# MCULeds.net
KiCad netlist of a schematic drawn in Altium Designer
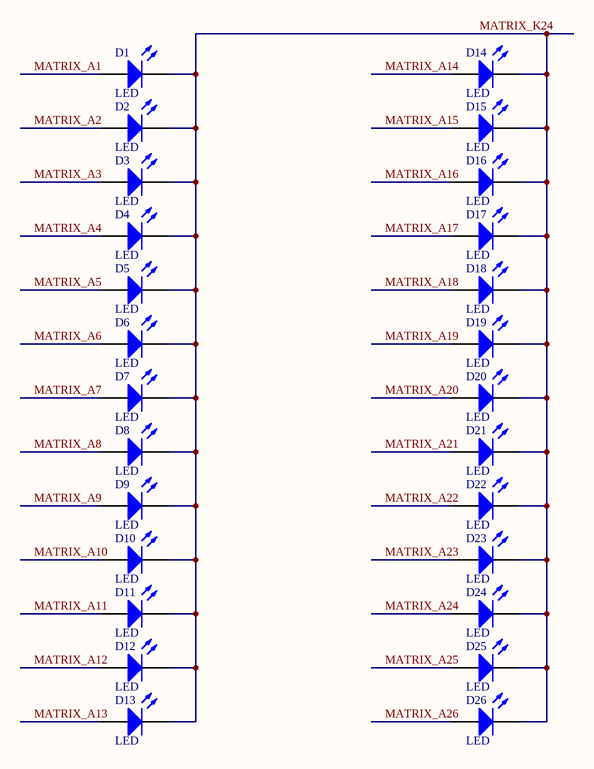
[diagram p0: MCULeds.SchDoc]

(export (version "E")
  (design (tool "Eeschema 10.0.6"))
  (components
    (comp (ref "D1")
      (value "LED")
      (footprint "led_0402")
      (description "Typical INFRARED GaAs LED")
      (fields (field (name "PUBLISHER") "Altium Limited"))
      (libsource (lib "Lib_Sch") (part "LED"))
    )
    (comp (ref "D2")
      (value "LED")
      (footprint "led_0402")
      (description "Typical INFRARED GaAs LED")
      (fields (field (name "PUBLISHER") "Altium Limited"))
      (libsource (lib "Lib_Sch") (part "LED"))
    )
    (comp (ref "D3")
      (value "LED")
      (footprint "led_0402")
      (description "Typical INFRARED GaAs LED")
      (fields (field (name "PUBLISHER") "Altium Limited"))
      (libsource (lib "Lib_Sch") (part "LED"))
    )
    (comp (ref "D4")
      (value "LED")
      (footprint "led_0402")
      (description "Typical INFRARED GaAs LED")
      (fields (field (name "PUBLISHER") "Altium Limited"))
      (libsource (lib "Lib_Sch") (part "LED"))
    )
    (comp (ref "D5")
      (value "LED")
      (footprint "led_0402")
      (description "Typical INFRARED GaAs LED")
      (fields (field (name "PUBLISHER") "Altium Limited"))
      (libsource (lib "Lib_Sch") (part "LED"))
    )
    (comp (ref "D6")
      (value "LED")
      (footprint "led_0402")
      (description "Typical INFRARED GaAs LED")
      (fields (field (name "PUBLISHER") "Altium Limited"))
      (libsource (lib "Lib_Sch") (part "LED"))
    )
    (comp (ref "D7")
      (value "LED")
      (footprint "led_0402")
      (description "Typical INFRARED GaAs LED")
      (fields (field (name "PUBLISHER") "Altium Limited"))
      (libsource (lib "Lib_Sch") (part "LED"))
    )
    (comp (ref "D8")
      (value "LED")
      (footprint "led_0402")
      (description "Typical INFRARED GaAs LED")
      (fields (field (name "PUBLISHER") "Altium Limited"))
      (libsource (lib "Lib_Sch") (part "LED"))
    )
    (comp (ref "D9")
      (value "LED")
      (footprint "led_0402")
      (description "Typical INFRARED GaAs LED")
      (fields (field (name "PUBLISHER") "Altium Limited"))
      (libsource (lib "Lib_Sch") (part "LED"))
    )
    (comp (ref "D10")
      (value "LED")
      (footprint "led_0402")
      (description "Typical INFRARED GaAs LED")
      (fields (field (name "PUBLISHER") "Altium Limited"))
      (libsource (lib "Lib_Sch") (part "LED"))
    )
    (comp (ref "D11")
      (value "LED")
      (footprint "led_0402")
      (description "Typical INFRARED GaAs LED")
      (fields (field (name "PUBLISHER") "Altium Limited"))
      (libsource (lib "Lib_Sch") (part "LED"))
    )
    (comp (ref "D12")
      (value "LED")
      (footprint "led_0402")
      (description "Typical INFRARED GaAs LED")
      (fields (field (name "PUBLISHER") "Altium Limited"))
      (libsource (lib "Lib_Sch") (part "LED"))
    )
    (comp (ref "D13")
      (value "LED")
      (footprint "led_0402")
      (description "Typical INFRARED GaAs LED")
      (fields (field (name "PUBLISHER") "Altium Limited"))
      (libsource (lib "Lib_Sch") (part "LED"))
    )
    (comp (ref "D14")
      (value "LED")
      (footprint "led_0402")
      (description "Typical INFRARED GaAs LED")
      (fields (field (name "PUBLISHER") "Altium Limited"))
      (libsource (lib "Lib_Sch") (part "LED"))
    )
    (comp (ref "D15")
      (value "LED")
      (footprint "led_0402")
      (description "Typical INFRARED GaAs LED")
      (fields (field (name "PUBLISHER") "Altium Limited"))
      (libsource (lib "Lib_Sch") (part "LED"))
    )
    (comp (ref "D16")
      (value "LED")
      (footprint "led_0402")
      (description "Typical INFRARED GaAs LED")
      (fields (field (name "PUBLISHER") "Altium Limited"))
      (libsource (lib "Lib_Sch") (part "LED"))
    )
    (comp (ref "D17")
      (value "LED")
      (footprint "led_0402")
      (description "Typical INFRARED GaAs LED")
      (fields (field (name "PUBLISHER") "Altium Limited"))
      (libsource (lib "Lib_Sch") (part "LED"))
    )
    (comp (ref "D18")
      (value "LED")
      (footprint "led_0402")
      (description "Typical INFRARED GaAs LED")
      (fields (field (name "PUBLISHER") "Altium Limited"))
      (libsource (lib "Lib_Sch") (part "LED"))
    )
    (comp (ref "D19")
      (value "LED")
      (footprint "led_0402")
      (description "Typical INFRARED GaAs LED")
      (fields (field (name "PUBLISHER") "Altium Limited"))
      (libsource (lib "Lib_Sch") (part "LED"))
    )
    (comp (ref "D20")
      (value "LED")
      (footprint "led_0402")
      (description "Typical INFRARED GaAs LED")
      (fields (field (name "PUBLISHER") "Altium Limited"))
      (libsource (lib "Lib_Sch") (part "LED"))
    )
    (comp (ref "D21")
      (value "LED")
      (footprint "led_0402")
      (description "Typical INFRARED GaAs LED")
      (fields (field (name "PUBLISHER") "Altium Limited"))
      (libsource (lib "Lib_Sch") (part "LED"))
    )
    (comp (ref "D22")
      (value "LED")
      (footprint "led_0402")
      (description "Typical INFRARED GaAs LED")
      (fields (field (name "PUBLISHER") "Altium Limited"))
      (libsource (lib "Lib_Sch") (part "LED"))
    )
    (comp (ref "D23")
      (value "LED")
      (footprint "led_0402")
      (description "Typical INFRARED GaAs LED")
      (fields (field (name "PUBLISHER") "Altium Limited"))
      (libsource (lib "Lib_Sch") (part "LED"))
    )
    (comp (ref "D24")
      (value "LED")
      (footprint "led_0402")
      (description "Typical INFRARED GaAs LED")
      (fields (field (name "PUBLISHER") "Altium Limited"))
      (libsource (lib "Lib_Sch") (part "LED"))
    )
    (comp (ref "D25")
      (value "LED")
      (footprint "led_0402")
      (description "Typical INFRARED GaAs LED")
      (fields (field (name "PUBLISHER") "Altium Limited"))
      (libsource (lib "Lib_Sch") (part "LED"))
    )
    (comp (ref "D26")
      (value "LED")
      (footprint "led_0402")
      (description "Typical INFRARED GaAs LED")
      (fields (field (name "PUBLISHER") "Altium Limited"))
      (libsource (lib "Lib_Sch") (part "LED"))
    )
  )
  (nets
    (net (code "1") (name "/MATRIX_A1") (class "Default")
      (node (ref "D1") (pin "A") (pinfunction "A_A") (pintype "passive"))
    )
    (net (code "2") (name "/MATRIX_A2") (class "Default")
      (node (ref "D2") (pin "A") (pinfunction "A_A") (pintype "passive"))
    )
    (net (code "3") (name "/MATRIX_A3") (class "Default")
      (node (ref "D3") (pin "A") (pinfunction "A_A") (pintype "passive"))
    )
    (net (code "4") (name "/MATRIX_A4") (class "Default")
      (node (ref "D4") (pin "A") (pinfunction "A_A") (pintype "passive"))
    )
    (net (code "5") (name "/MATRIX_A5") (class "Default")
      (node (ref "D5") (pin "A") (pinfunction "A_A") (pintype "passive"))
    )
    (net (code "6") (name "/MATRIX_A6") (class "Default")
      (node (ref "D6") (pin "A") (pinfunction "A_A") (pintype "passive"))
    )
    (net (code "7") (name "/MATRIX_A7") (class "Default")
      (node (ref "D7") (pin "A") (pinfunction "A_A") (pintype "passive"))
    )
    (net (code "8") (name "/MATRIX_A8") (class "Default")
      (node (ref "D8") (pin "A") (pinfunction "A_A") (pintype "passive"))
    )
    (net (code "9") (name "/MATRIX_A9") (class "Default")
      (node (ref "D9") (pin "A") (pinfunction "A_A") (pintype "passive"))
    )
    (net (code "10") (name "/MATRIX_A10") (class "Default")
      (node (ref "D10") (pin "A") (pinfunction "A_A") (pintype "passive"))
    )
    (net (code "11") (name "/MATRIX_A11") (class "Default")
      (node (ref "D11") (pin "A") (pinfunction "A_A") (pintype "passive"))
    )
    (net (code "12") (name "/MATRIX_A12") (class "Default")
      (node (ref "D12") (pin "A") (pinfunction "A_A") (pintype "passive"))
    )
    (net (code "13") (name "/MATRIX_A13") (class "Default")
      (node (ref "D13") (pin "A") (pinfunction "A_A") (pintype "passive"))
    )
    (net (code "14") (name "/MATRIX_A14") (class "Default")
      (node (ref "D14") (pin "A") (pinfunction "A_A") (pintype "passive"))
    )
    (net (code "15") (name "/MATRIX_A15") (class "Default")
      (node (ref "D15") (pin "A") (pinfunction "A_A") (pintype "passive"))
    )
    (net (code "16") (name "/MATRIX_A16") (class "Default")
      (node (ref "D16") (pin "A") (pinfunction "A_A") (pintype "passive"))
    )
    (net (code "17") (name "/MATRIX_A17") (class "Default")
      (node (ref "D17") (pin "A") (pinfunction "A_A") (pintype "passive"))
    )
    (net (code "18") (name "/MATRIX_A18") (class "Default")
      (node (ref "D18") (pin "A") (pinfunction "A_A") (pintype "passive"))
    )
    (net (code "19") (name "/MATRIX_A19") (class "Default")
      (node (ref "D19") (pin "A") (pinfunction "A_A") (pintype "passive"))
    )
    (net (code "20") (name "/MATRIX_A20") (class "Default")
      (node (ref "D20") (pin "A") (pinfunction "A_A") (pintype "passive"))
    )
    (net (code "21") (name "/MATRIX_A21") (class "Default")
      (node (ref "D21") (pin "A") (pinfunction "A_A") (pintype "passive"))
    )
    (net (code "22") (name "/MATRIX_A22") (class "Default")
      (node (ref "D22") (pin "A") (pinfunction "A_A") (pintype "passive"))
    )
    (net (code "23") (name "/MATRIX_A23") (class "Default")
      (node (ref "D23") (pin "A") (pinfunction "A_A") (pintype "passive"))
    )
    (net (code "24") (name "/MATRIX_A24") (class "Default")
      (node (ref "D24") (pin "A") (pinfunction "A_A") (pintype "passive"))
    )
    (net (code "25") (name "/MATRIX_A25") (class "Default")
      (node (ref "D25") (pin "A") (pinfunction "A_A") (pintype "passive"))
    )
    (net (code "26") (name "/MATRIX_A26") (class "Default")
      (node (ref "D26") (pin "A") (pinfunction "A_A") (pintype "passive"))
    )
    (net (code "27") (name "/MATRIX_K24") (class "Default")
      (node (ref "D1") (pin "K") (pinfunction "K_K") (pintype "passive"))
      (node (ref "D10") (pin "K") (pinfunction "K_K") (pintype "passive"))
      (node (ref "D11") (pin "K") (pinfunction "K_K") (pintype "passive"))
      (node (ref "D12") (pin "K") (pinfunction "K_K") (pintype "passive"))
      (node (ref "D13") (pin "K") (pinfunction "K_K") (pintype "passive"))
      (node (ref "D14") (pin "K") (pinfunction "K_K") (pintype "passive"))
      (node (ref "D15") (pin "K") (pinfunction "K_K") (pintype "passive"))
      (node (ref "D16") (pin "K") (pinfunction "K_K") (pintype "passive"))
      (node (ref "D17") (pin "K") (pinfunction "K_K") (pintype "passive"))
      (node (ref "D18") (pin "K") (pinfunction "K_K") (pintype "passive"))
      (node (ref "D19") (pin "K") (pinfunction "K_K") (pintype "passive"))
      (node (ref "D2") (pin "K") (pinfunction "K_K") (pintype "passive"))
      (node (ref "D20") (pin "K") (pinfunction "K_K") (pintype "passive"))
      (node (ref "D21") (pin "K") (pinfunction "K_K") (pintype "passive"))
      (node (ref "D22") (pin "K") (pinfunction "K_K") (pintype "passive"))
      (node (ref "D23") (pin "K") (pinfunction "K_K") (pintype "passive"))
      (node (ref "D24") (pin "K") (pinfunction "K_K") (pintype "passive"))
      (node (ref "D25") (pin "K") (pinfunction "K_K") (pintype "passive"))
      (node (ref "D26") (pin "K") (pinfunction "K_K") (pintype "passive"))
      (node (ref "D3") (pin "K") (pinfunction "K_K") (pintype "passive"))
      (node (ref "D4") (pin "K") (pinfunction "K_K") (pintype "passive"))
      (node (ref "D5") (pin "K") (pinfunction "K_K") (pintype "passive"))
      (node (ref "D6") (pin "K") (pinfunction "K_K") (pintype "passive"))
      (node (ref "D7") (pin "K") (pinfunction "K_K") (pintype "passive"))
      (node (ref "D8") (pin "K") (pinfunction "K_K") (pintype "passive"))
      (node (ref "D9") (pin "K") (pinfunction "K_K") (pintype "passive"))
    )
  )
)
